# scorbot_jcb.net
KiCad netlist of a schematic drawn in EAGLE
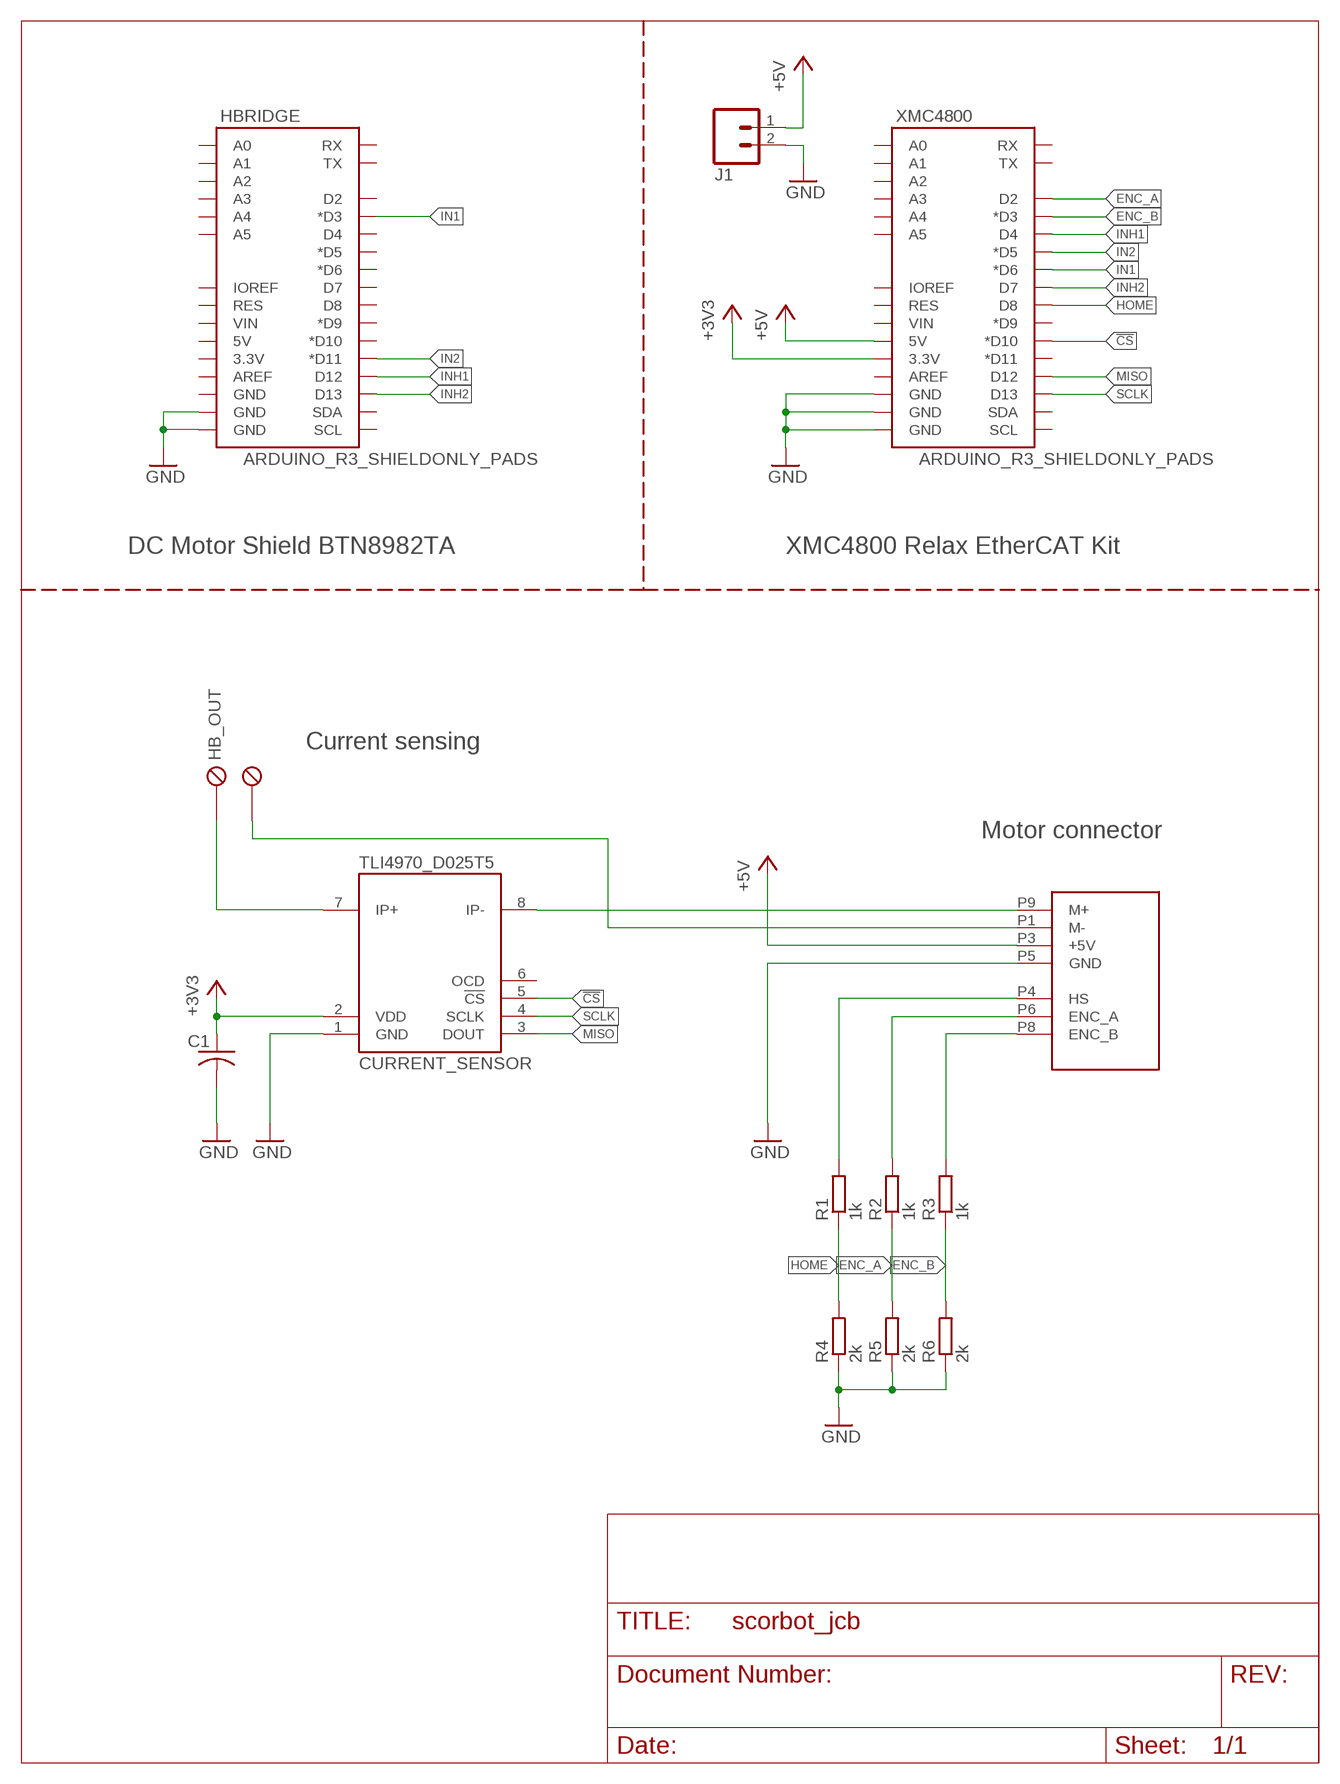
[diagram p0: schematic, sheet 1]

(export (version "E")
  (design (tool "Eeschema 10.0.6"))
  (components
    (comp (ref "C1")
      (value "C-US025-025X050")
      (footprint "eagle-import:C025-025X050")
      (libsource (lib "eagle-import") (part "C-US025-025X050"))
    )
    (comp (ref "CURRENT_SENSOR")
      (value "TLI4970_D025T5")
      (footprint "eagle-import:TLI4970_D025T5")
      (libsource (lib "eagle-import") (part "TLI4970_D025T5"))
    )
    (comp (ref "DB9")
      (value "SCORBOT_CONNECTOR")
      (footprint "eagle-import:XM3-LS")
      (libsource (lib "eagle-import") (part "SCORBOT_CONNECTOR"))
    )
    (comp (ref "HBRIDGE")
      (value "ARDUINO_R3_SHIELDONLY_PADS")
      (footprint "eagle-import:UNO_R3_SHIELD_ONLY_PADS")
      (libsource (lib "eagle-import") (part "ARDUINO_R3_SHIELDONLY_PADS"))
    )
    (comp (ref "HB_OUT")
      (value "METALTEX-2SHORT")
      (footprint "eagle-import:METALTEX-2S")
      (libsource (lib "eagle-import") (part "METALTEX-2SHORT"))
    )
    (comp (ref "J1")
      (value "M02LOCK_LONGPADS")
      (footprint "eagle-import:1X02_LOCK_LONGPADS")
      (libsource (lib "eagle-import") (part "M02LOCK_LONGPADS"))
    )
    (comp (ref "R1")
      (value "1k")
      (footprint "eagle-import:0309_12")
      (libsource (lib "eagle-import") (part "R-EU_0309/12"))
    )
    (comp (ref "R2")
      (value "1k")
      (footprint "eagle-import:0309_12")
      (libsource (lib "eagle-import") (part "R-EU_0309/12"))
    )
    (comp (ref "R3")
      (value "1k")
      (footprint "eagle-import:0309_12")
      (libsource (lib "eagle-import") (part "R-EU_0309/12"))
    )
    (comp (ref "R4")
      (value "2k")
      (footprint "eagle-import:0309_12")
      (libsource (lib "eagle-import") (part "R-EU_0309/12"))
    )
    (comp (ref "R5")
      (value "2k")
      (footprint "eagle-import:0309_12")
      (libsource (lib "eagle-import") (part "R-EU_0309/12"))
    )
    (comp (ref "R6")
      (value "2k")
      (footprint "eagle-import:0309_12")
      (libsource (lib "eagle-import") (part "R-EU_0309/12"))
    )
    (comp (ref "XMC4800")
      (value "ARDUINO_R3_SHIELDONLY_PADS")
      (footprint "eagle-import:UNO_R3_SHIELD_ONLY_PADS")
      (libsource (lib "eagle-import") (part "ARDUINO_R3_SHIELDONLY_PADS"))
    )
  )
  (nets
    (net (code "1") (name "+3V3") (class "Default")
      (node (ref "C1") (pin "1") (pinfunction "1_1") (pintype "passive"))
      (node (ref "CURRENT_SENSOR") (pin "2") (pinfunction "VDD_2") (pintype "power_in"))
      (node (ref "XMC4800") (pin "3.3V") (pinfunction "3.3V_3.3V") (pintype "bidirectional"))
    )
    (net (code "2") (name "+5V") (class "Default")
      (node (ref "DB9") (pin "P3") (pinfunction "+5V_P3") (pintype "power_in"))
      (node (ref "J1") (pin "1") (pinfunction "1_1") (pintype "passive"))
      (node (ref "XMC4800") (pin "5V") (pinfunction "5V_5V") (pintype "bidirectional"))
    )
    (net (code "3") (name "/~{CS}") (class "Default")
      (node (ref "CURRENT_SENSOR") (pin "5") (pinfunction "~{CS}_5") (pintype "input"))
      (node (ref "XMC4800") (pin "D10") (pinfunction "*D10_D10") (pintype "bidirectional"))
    )
    (net (code "4") (name "ENC_A") (class "Default")
      (node (ref "R2") (pin "1") (pinfunction "1_1") (pintype "passive"))
      (node (ref "R5") (pin "2") (pinfunction "2_2") (pintype "passive"))
      (node (ref "XMC4800") (pin "D2") (pinfunction "D2_D2") (pintype "bidirectional"))
    )
    (net (code "5") (name "ENC_B") (class "Default")
      (node (ref "R3") (pin "1") (pinfunction "1_1") (pintype "passive"))
      (node (ref "R6") (pin "2") (pinfunction "2_2") (pintype "passive"))
      (node (ref "XMC4800") (pin "D3") (pinfunction "*D3_D3") (pintype "bidirectional"))
    )
    (net (code "6") (name "GND") (class "Default")
      (node (ref "C1") (pin "2") (pinfunction "2_2") (pintype "passive"))
      (node (ref "CURRENT_SENSOR") (pin "1") (pinfunction "GND_1") (pintype "power_in"))
      (node (ref "DB9") (pin "P5") (pinfunction "GND_P5") (pintype "power_in"))
      (node (ref "HBRIDGE") (pin "GND@0") (pinfunction "GND_GND@0") (pintype "bidirectional"))
      (node (ref "HBRIDGE") (pin "GND@1") (pinfunction "GND_GND@1") (pintype "bidirectional"))
      (node (ref "J1") (pin "2") (pinfunction "2_2") (pintype "passive"))
      (node (ref "R4") (pin "1") (pinfunction "1_1") (pintype "passive"))
      (node (ref "R5") (pin "1") (pinfunction "1_1") (pintype "passive"))
      (node (ref "R6") (pin "1") (pinfunction "1_1") (pintype "passive"))
      (node (ref "XMC4800") (pin "GND@0") (pinfunction "GND_GND@0") (pintype "bidirectional"))
      (node (ref "XMC4800") (pin "GND@1") (pinfunction "GND_GND@1") (pintype "bidirectional"))
      (node (ref "XMC4800") (pin "GND@2") (pinfunction "GND_GND@2") (pintype "bidirectional"))
    )
    (net (code "7") (name "HOME") (class "Default")
      (node (ref "R1") (pin "1") (pinfunction "1_1") (pintype "passive"))
      (node (ref "R4") (pin "2") (pinfunction "2_2") (pintype "passive"))
      (node (ref "XMC4800") (pin "D8") (pinfunction "D8_D8") (pintype "bidirectional"))
    )
    (net (code "8") (name "IN1") (class "Default")
      (node (ref "HBRIDGE") (pin "D3") (pinfunction "*D3_D3") (pintype "bidirectional"))
      (node (ref "XMC4800") (pin "D6") (pinfunction "*D6_D6") (pintype "bidirectional"))
    )
    (net (code "9") (name "IN2") (class "Default")
      (node (ref "HBRIDGE") (pin "D11") (pinfunction "*D11_D11") (pintype "bidirectional"))
      (node (ref "XMC4800") (pin "D5") (pinfunction "*D5_D5") (pintype "bidirectional"))
    )
    (net (code "10") (name "INH1") (class "Default")
      (node (ref "HBRIDGE") (pin "D12") (pinfunction "D12_D12") (pintype "bidirectional"))
      (node (ref "XMC4800") (pin "D4") (pinfunction "D4_D4") (pintype "bidirectional"))
    )
    (net (code "11") (name "INH2") (class "Default")
      (node (ref "HBRIDGE") (pin "D13") (pinfunction "D13_D13") (pintype "bidirectional"))
      (node (ref "XMC4800") (pin "D7") (pinfunction "D7_D7") (pintype "bidirectional"))
    )
    (net (code "12") (name "MISO") (class "Default")
      (node (ref "CURRENT_SENSOR") (pin "3") (pinfunction "DOUT_3") (pintype "output"))
      (node (ref "XMC4800") (pin "D12") (pinfunction "D12_D12") (pintype "bidirectional"))
    )
    (net (code "13") (name "Net-(CURRENT_SENSOR-IP+)") (class "Default")
      (node (ref "CURRENT_SENSOR") (pin "7") (pinfunction "IP+_7") (pintype "input"))
      (node (ref "HB_OUT") (pin "P1") (pinfunction "P1_P1") (pintype "bidirectional"))
    )
    (net (code "14") (name "Net-(CURRENT_SENSOR-IP-)") (class "Default")
      (node (ref "CURRENT_SENSOR") (pin "8") (pinfunction "IP-_8") (pintype "output"))
      (node (ref "DB9") (pin "P9") (pinfunction "M+_P9") (pintype "power_in"))
    )
    (net (code "15") (name "Net-(DB9-ENC_A)") (class "Default")
      (node (ref "DB9") (pin "P6") (pinfunction "ENC_A_P6") (pintype "bidirectional"))
      (node (ref "R2") (pin "2") (pinfunction "2_2") (pintype "passive"))
    )
    (net (code "16") (name "Net-(DB9-ENC_B)") (class "Default")
      (node (ref "DB9") (pin "P8") (pinfunction "ENC_B_P8") (pintype "bidirectional"))
      (node (ref "R3") (pin "2") (pinfunction "2_2") (pintype "passive"))
    )
    (net (code "17") (name "Net-(DB9-HS)") (class "Default")
      (node (ref "DB9") (pin "P4") (pinfunction "HS_P4") (pintype "bidirectional"))
      (node (ref "R1") (pin "2") (pinfunction "2_2") (pintype "passive"))
    )
    (net (code "18") (name "Net-(DB9-M-)") (class "Default")
      (node (ref "DB9") (pin "P1") (pinfunction "M-_P1") (pintype "power_in"))
      (node (ref "HB_OUT") (pin "P2") (pinfunction "P2_P2") (pintype "bidirectional"))
    )
    (net (code "19") (name "SCLK") (class "Default")
      (node (ref "CURRENT_SENSOR") (pin "4") (pinfunction "SCLK_4") (pintype "input"))
      (node (ref "XMC4800") (pin "D13") (pinfunction "D13_D13") (pintype "bidirectional"))
    )
    (net (code "20") (name "unconnected-(CURRENT_SENSOR-OCD-Pad6)") (class "Default")
      (node (ref "CURRENT_SENSOR") (pin "6") (pinfunction "OCD_6") (pintype "output"))
    )
    (net (code "21") (name "unconnected-(HBRIDGE-*D5-PadD5)") (class "Default")
      (node (ref "HBRIDGE") (pin "D5") (pinfunction "*D5_D5") (pintype "bidirectional"))
    )
    (net (code "22") (name "unconnected-(HBRIDGE-*D6-PadD6)") (class "Default")
      (node (ref "HBRIDGE") (pin "D6") (pinfunction "*D6_D6") (pintype "bidirectional"))
    )
    (net (code "23") (name "unconnected-(HBRIDGE-*D9-PadD9)") (class "Default")
      (node (ref "HBRIDGE") (pin "D9") (pinfunction "*D9_D9") (pintype "bidirectional"))
    )
    (net (code "24") (name "unconnected-(HBRIDGE-*D10-PadD10)") (class "Default")
      (node (ref "HBRIDGE") (pin "D10") (pinfunction "*D10_D10") (pintype "bidirectional"))
    )
    (net (code "25") (name "unconnected-(HBRIDGE-GND-PadGND@2)") (class "Default")
      (node (ref "HBRIDGE") (pin "GND@2") (pinfunction "GND_GND@2") (pintype "bidirectional"))
    )
    (net (code "26") (name "unconnected-(HBRIDGE-Pad3.3V)") (class "Default")
      (node (ref "HBRIDGE") (pin "3.3V") (pinfunction "3.3V_3.3V") (pintype "bidirectional"))
    )
    (net (code "27") (name "unconnected-(HBRIDGE-Pad5V)") (class "Default")
      (node (ref "HBRIDGE") (pin "5V") (pinfunction "5V_5V") (pintype "bidirectional"))
    )
    (net (code "28") (name "unconnected-(HBRIDGE-PadA0)") (class "Default")
      (node (ref "HBRIDGE") (pin "A0") (pinfunction "A0_A0") (pintype "bidirectional"))
    )
    (net (code "29") (name "unconnected-(HBRIDGE-PadA1)") (class "Default")
      (node (ref "HBRIDGE") (pin "A1") (pinfunction "A1_A1") (pintype "bidirectional"))
    )
    (net (code "30") (name "unconnected-(HBRIDGE-PadA2)") (class "Default")
      (node (ref "HBRIDGE") (pin "A2") (pinfunction "A2_A2") (pintype "bidirectional"))
    )
    (net (code "31") (name "unconnected-(HBRIDGE-PadA3)") (class "Default")
      (node (ref "HBRIDGE") (pin "A3") (pinfunction "A3_A3") (pintype "bidirectional"))
    )
    (net (code "32") (name "unconnected-(HBRIDGE-PadA4)") (class "Default")
      (node (ref "HBRIDGE") (pin "A4") (pinfunction "A4_A4") (pintype "bidirectional"))
    )
    (net (code "33") (name "unconnected-(HBRIDGE-PadA5)") (class "Default")
      (node (ref "HBRIDGE") (pin "A5") (pinfunction "A5_A5") (pintype "bidirectional"))
    )
    (net (code "34") (name "unconnected-(HBRIDGE-PadAREF)") (class "Default")
      (node (ref "HBRIDGE") (pin "AREF") (pinfunction "AREF_AREF") (pintype "bidirectional"))
    )
    (net (code "35") (name "unconnected-(HBRIDGE-PadD2)") (class "Default")
      (node (ref "HBRIDGE") (pin "D2") (pinfunction "D2_D2") (pintype "bidirectional"))
    )
    (net (code "36") (name "unconnected-(HBRIDGE-PadD4)") (class "Default")
      (node (ref "HBRIDGE") (pin "D4") (pinfunction "D4_D4") (pintype "bidirectional"))
    )
    (net (code "37") (name "unconnected-(HBRIDGE-PadD7)") (class "Default")
      (node (ref "HBRIDGE") (pin "D7") (pinfunction "D7_D7") (pintype "bidirectional"))
    )
    (net (code "38") (name "unconnected-(HBRIDGE-PadD8)") (class "Default")
      (node (ref "HBRIDGE") (pin "D8") (pinfunction "D8_D8") (pintype "bidirectional"))
    )
    (net (code "39") (name "unconnected-(HBRIDGE-PadIOREF)") (class "Default")
      (node (ref "HBRIDGE") (pin "IOREF") (pinfunction "IOREF_IOREF") (pintype "bidirectional"))
    )
    (net (code "40") (name "unconnected-(HBRIDGE-PadRES)") (class "Default")
      (node (ref "HBRIDGE") (pin "RES") (pinfunction "RES_RES") (pintype "bidirectional"))
    )
    (net (code "41") (name "unconnected-(HBRIDGE-PadRX)") (class "Default")
      (node (ref "HBRIDGE") (pin "RX") (pinfunction "RX_RX") (pintype "bidirectional"))
    )
    (net (code "42") (name "unconnected-(HBRIDGE-PadSCL)") (class "Default")
      (node (ref "HBRIDGE") (pin "SCL") (pinfunction "SCL_SCL") (pintype "bidirectional"))
    )
    (net (code "43") (name "unconnected-(HBRIDGE-PadSDA)") (class "Default")
      (node (ref "HBRIDGE") (pin "SDA") (pinfunction "SDA_SDA") (pintype "bidirectional"))
    )
    (net (code "44") (name "unconnected-(HBRIDGE-PadTX)") (class "Default")
      (node (ref "HBRIDGE") (pin "TX") (pinfunction "TX_TX") (pintype "bidirectional"))
    )
    (net (code "45") (name "unconnected-(HBRIDGE-PadVIN)") (class "Default")
      (node (ref "HBRIDGE") (pin "VIN") (pinfunction "VIN_VIN") (pintype "bidirectional"))
    )
    (net (code "46") (name "unconnected-(XMC4800-*D9-PadD9)") (class "Default")
      (node (ref "XMC4800") (pin "D9") (pinfunction "*D9_D9") (pintype "bidirectional"))
    )
    (net (code "47") (name "unconnected-(XMC4800-*D11-PadD11)") (class "Default")
      (node (ref "XMC4800") (pin "D11") (pinfunction "*D11_D11") (pintype "bidirectional"))
    )
    (net (code "48") (name "unconnected-(XMC4800-PadA0)") (class "Default")
      (node (ref "XMC4800") (pin "A0") (pinfunction "A0_A0") (pintype "bidirectional"))
    )
    (net (code "49") (name "unconnected-(XMC4800-PadA1)") (class "Default")
      (node (ref "XMC4800") (pin "A1") (pinfunction "A1_A1") (pintype "bidirectional"))
    )
    (net (code "50") (name "unconnected-(XMC4800-PadA2)") (class "Default")
      (node (ref "XMC4800") (pin "A2") (pinfunction "A2_A2") (pintype "bidirectional"))
    )
    (net (code "51") (name "unconnected-(XMC4800-PadA3)") (class "Default")
      (node (ref "XMC4800") (pin "A3") (pinfunction "A3_A3") (pintype "bidirectional"))
    )
    (net (code "52") (name "unconnected-(XMC4800-PadA4)") (class "Default")
      (node (ref "XMC4800") (pin "A4") (pinfunction "A4_A4") (pintype "bidirectional"))
    )
    (net (code "53") (name "unconnected-(XMC4800-PadA5)") (class "Default")
      (node (ref "XMC4800") (pin "A5") (pinfunction "A5_A5") (pintype "bidirectional"))
    )
    (net (code "54") (name "unconnected-(XMC4800-PadAREF)") (class "Default")
      (node (ref "XMC4800") (pin "AREF") (pinfunction "AREF_AREF") (pintype "bidirectional"))
    )
    (net (code "55") (name "unconnected-(XMC4800-PadIOREF)") (class "Default")
      (node (ref "XMC4800") (pin "IOREF") (pinfunction "IOREF_IOREF") (pintype "bidirectional"))
    )
    (net (code "56") (name "unconnected-(XMC4800-PadRES)") (class "Default")
      (node (ref "XMC4800") (pin "RES") (pinfunction "RES_RES") (pintype "bidirectional"))
    )
    (net (code "57") (name "unconnected-(XMC4800-PadRX)") (class "Default")
      (node (ref "XMC4800") (pin "RX") (pinfunction "RX_RX") (pintype "bidirectional"))
    )
    (net (code "58") (name "unconnected-(XMC4800-PadSCL)") (class "Default")
      (node (ref "XMC4800") (pin "SCL") (pinfunction "SCL_SCL") (pintype "bidirectional"))
    )
    (net (code "59") (name "unconnected-(XMC4800-PadSDA)") (class "Default")
      (node (ref "XMC4800") (pin "SDA") (pinfunction "SDA_SDA") (pintype "bidirectional"))
    )
    (net (code "60") (name "unconnected-(XMC4800-PadTX)") (class "Default")
      (node (ref "XMC4800") (pin "TX") (pinfunction "TX_TX") (pintype "bidirectional"))
    )
    (net (code "61") (name "unconnected-(XMC4800-PadVIN)") (class "Default")
      (node (ref "XMC4800") (pin "VIN") (pinfunction "VIN_VIN") (pintype "bidirectional"))
    )
  )
)
